# Firefly-Box.net
KiCad netlist of a schematic drawn in EAGLE
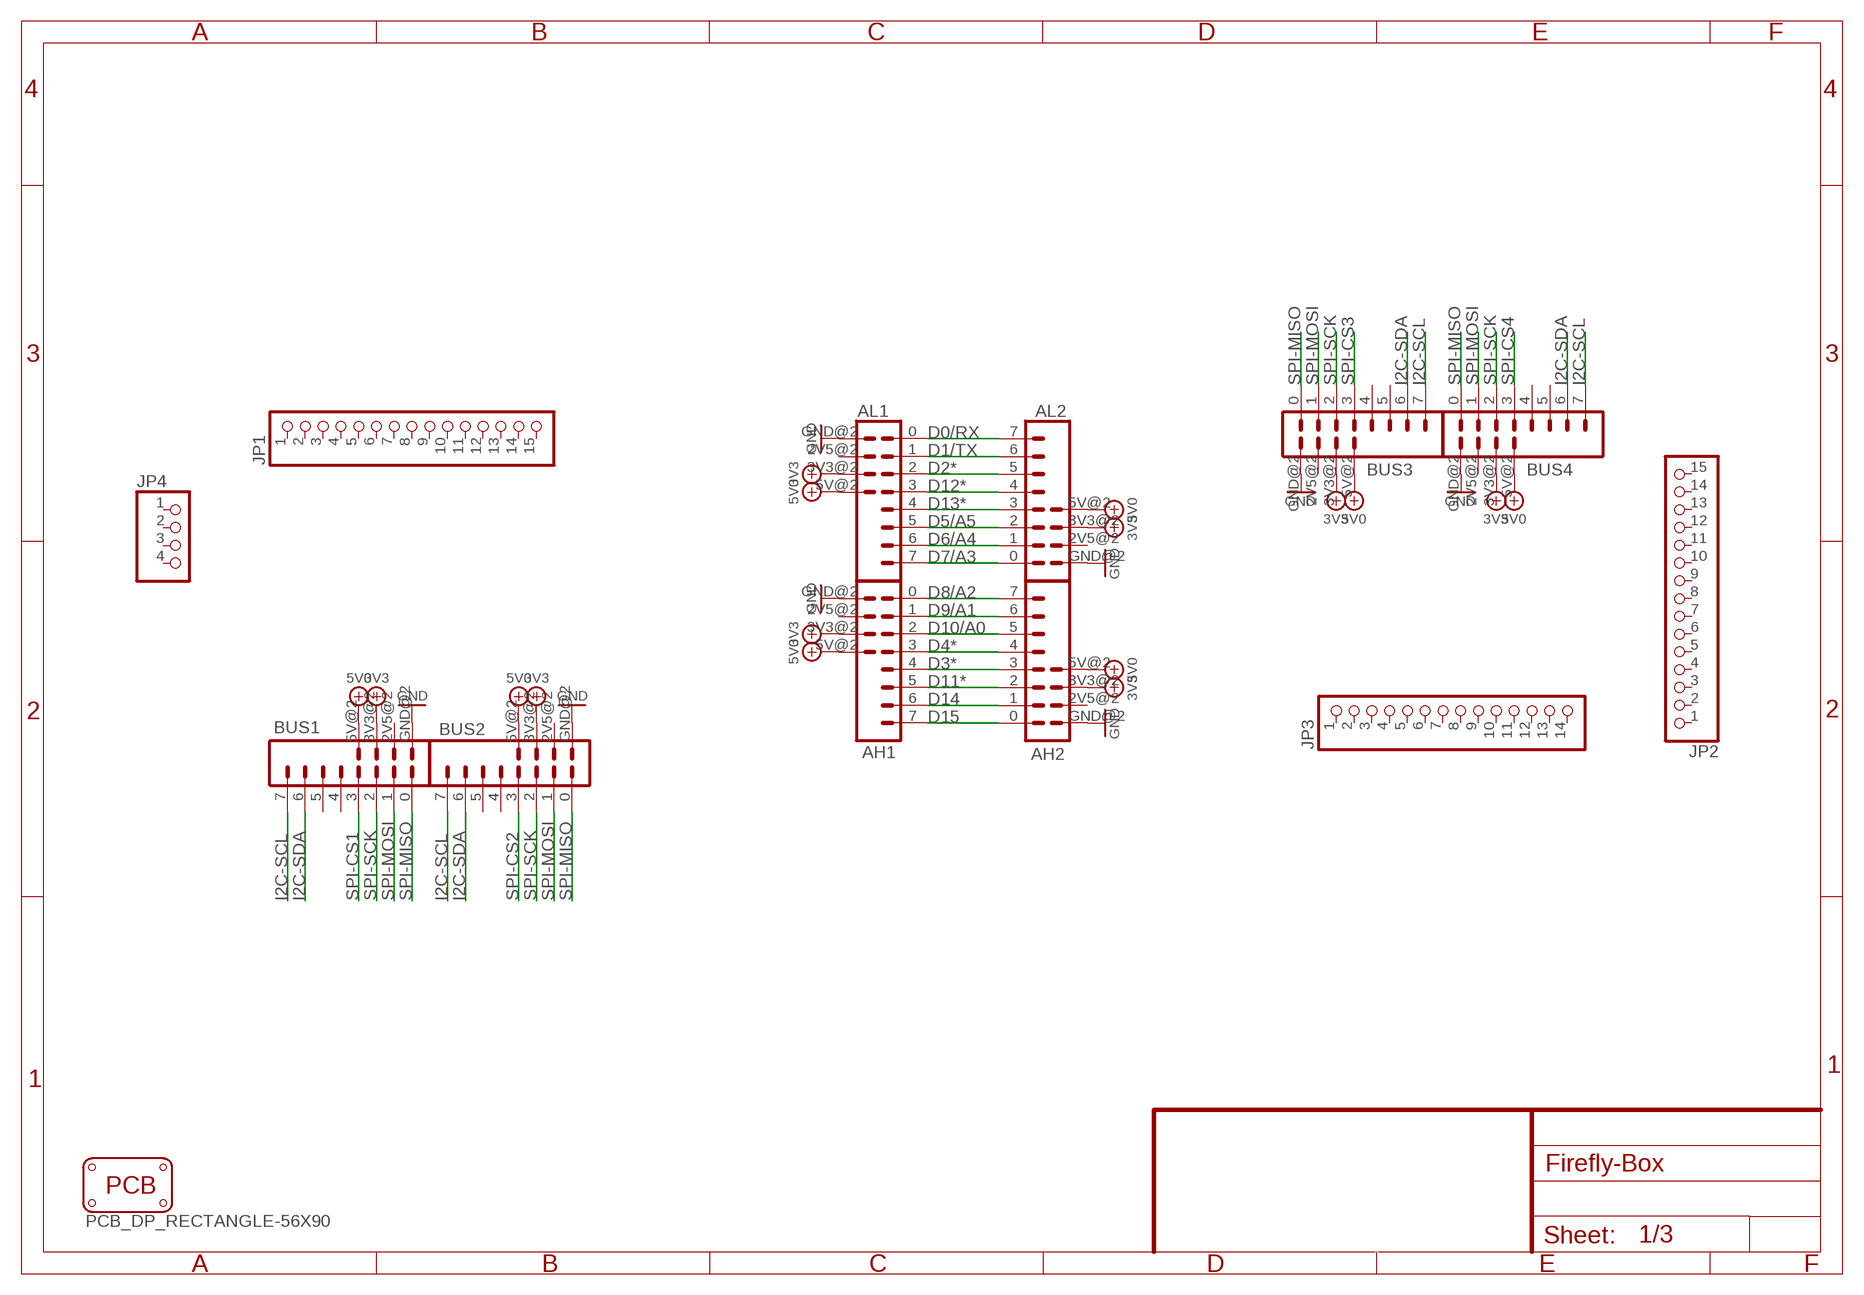
[diagram p0: schematic, sheet 1]
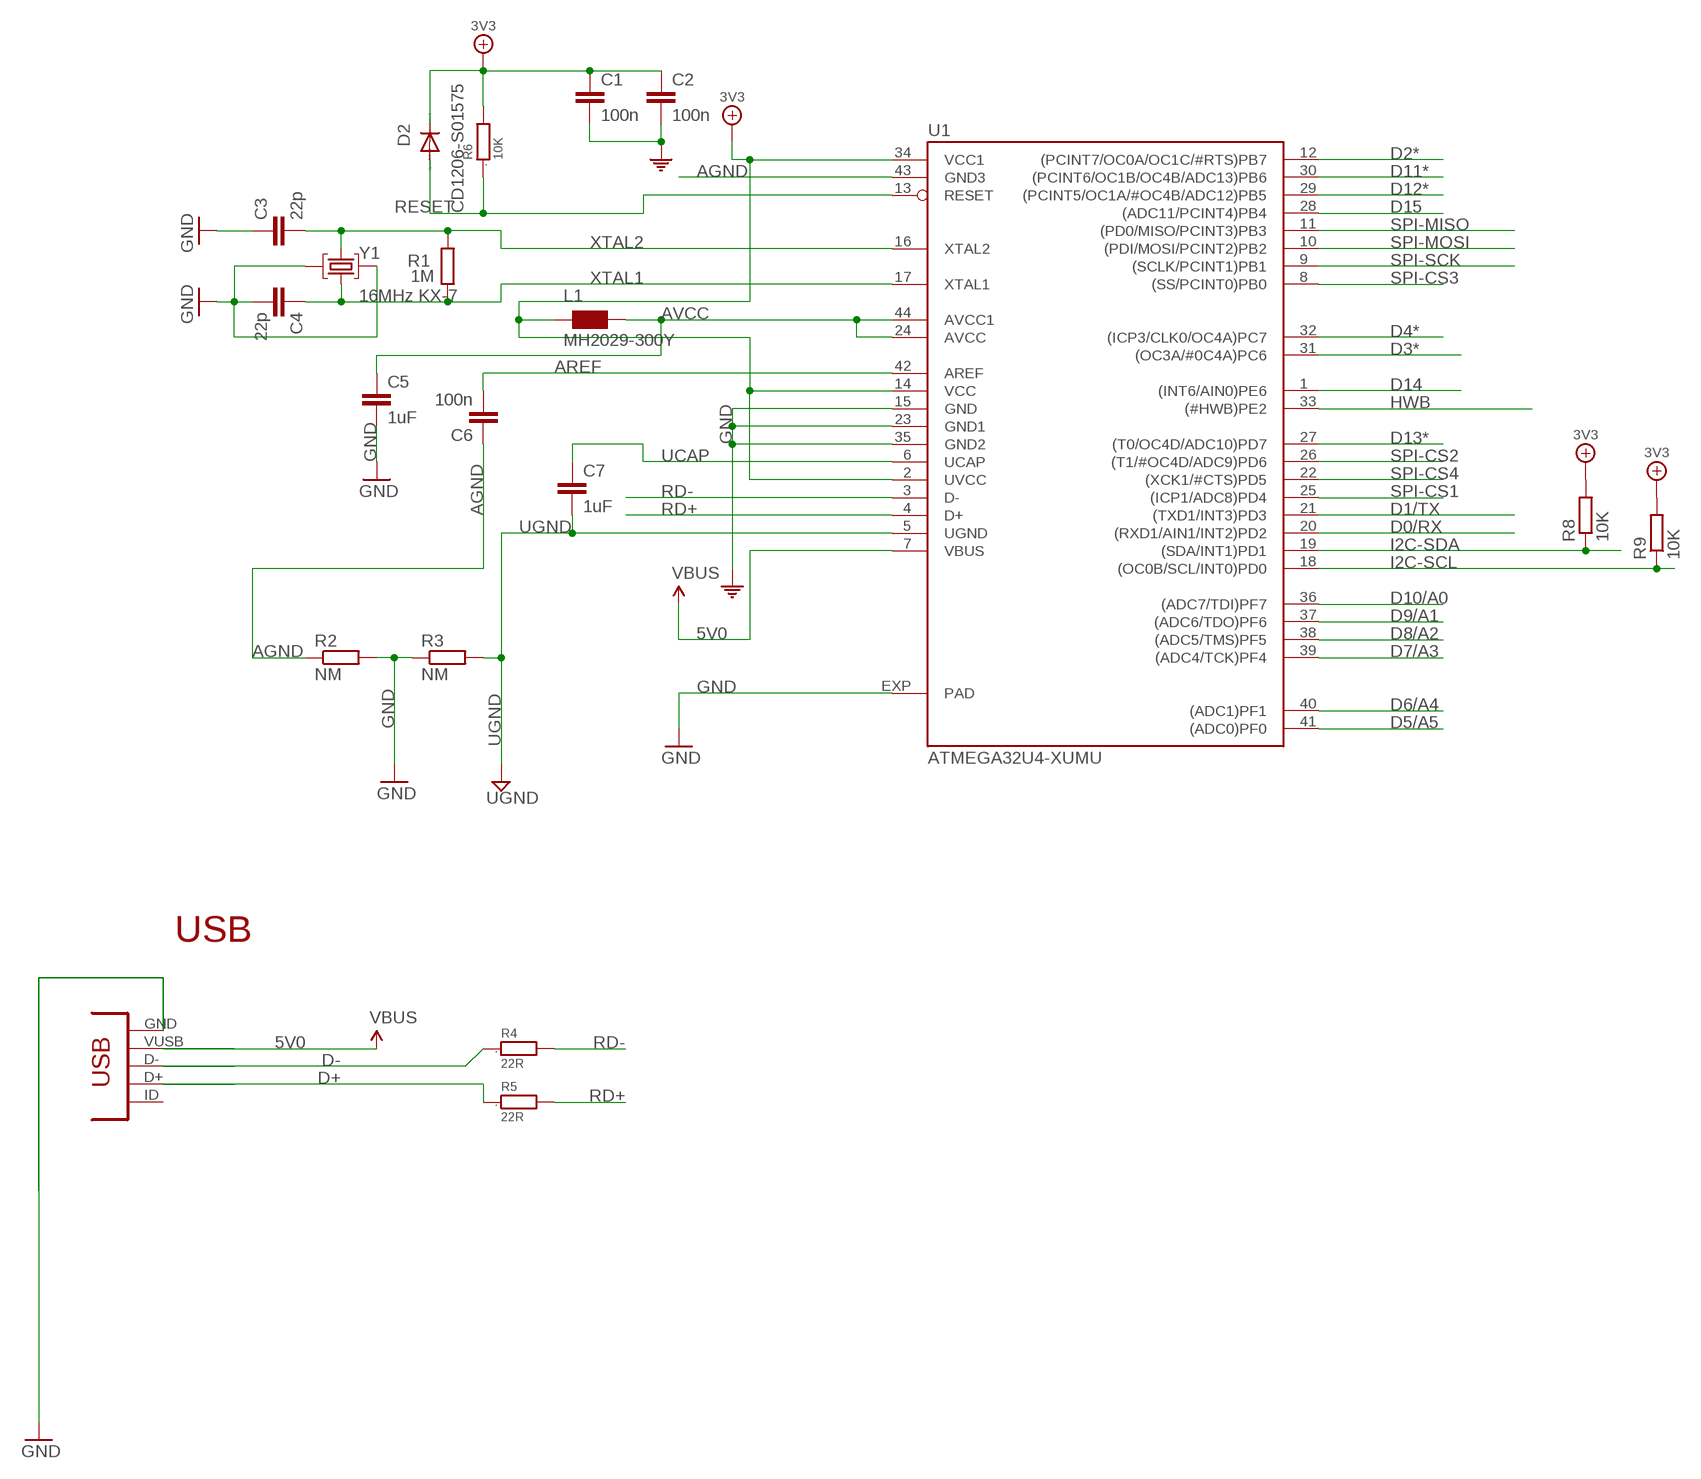
[diagram p1: schematic, sheet 2, part 1 of 2]
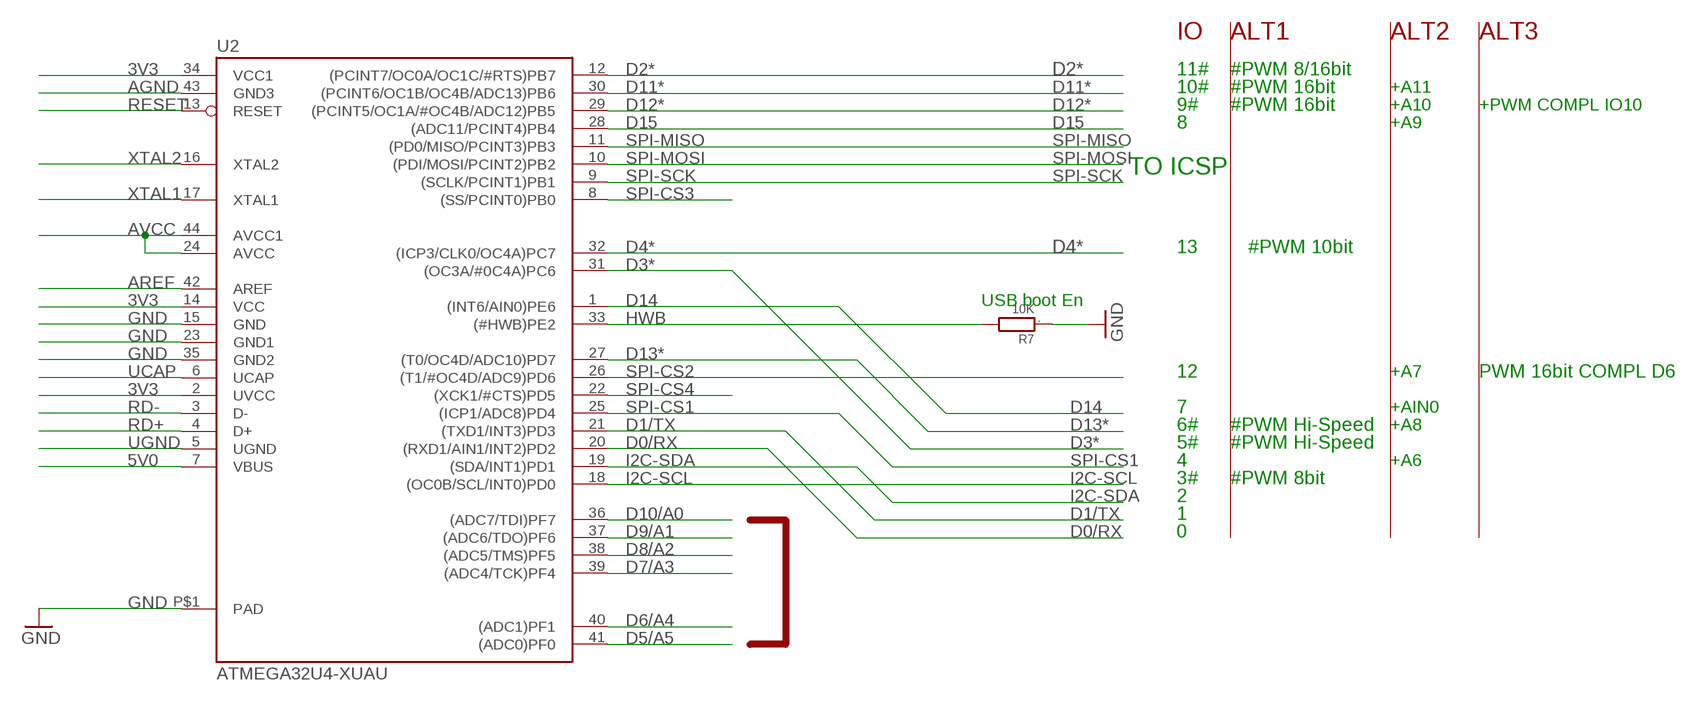
[diagram p2: schematic, sheet 2, part 2 of 2]
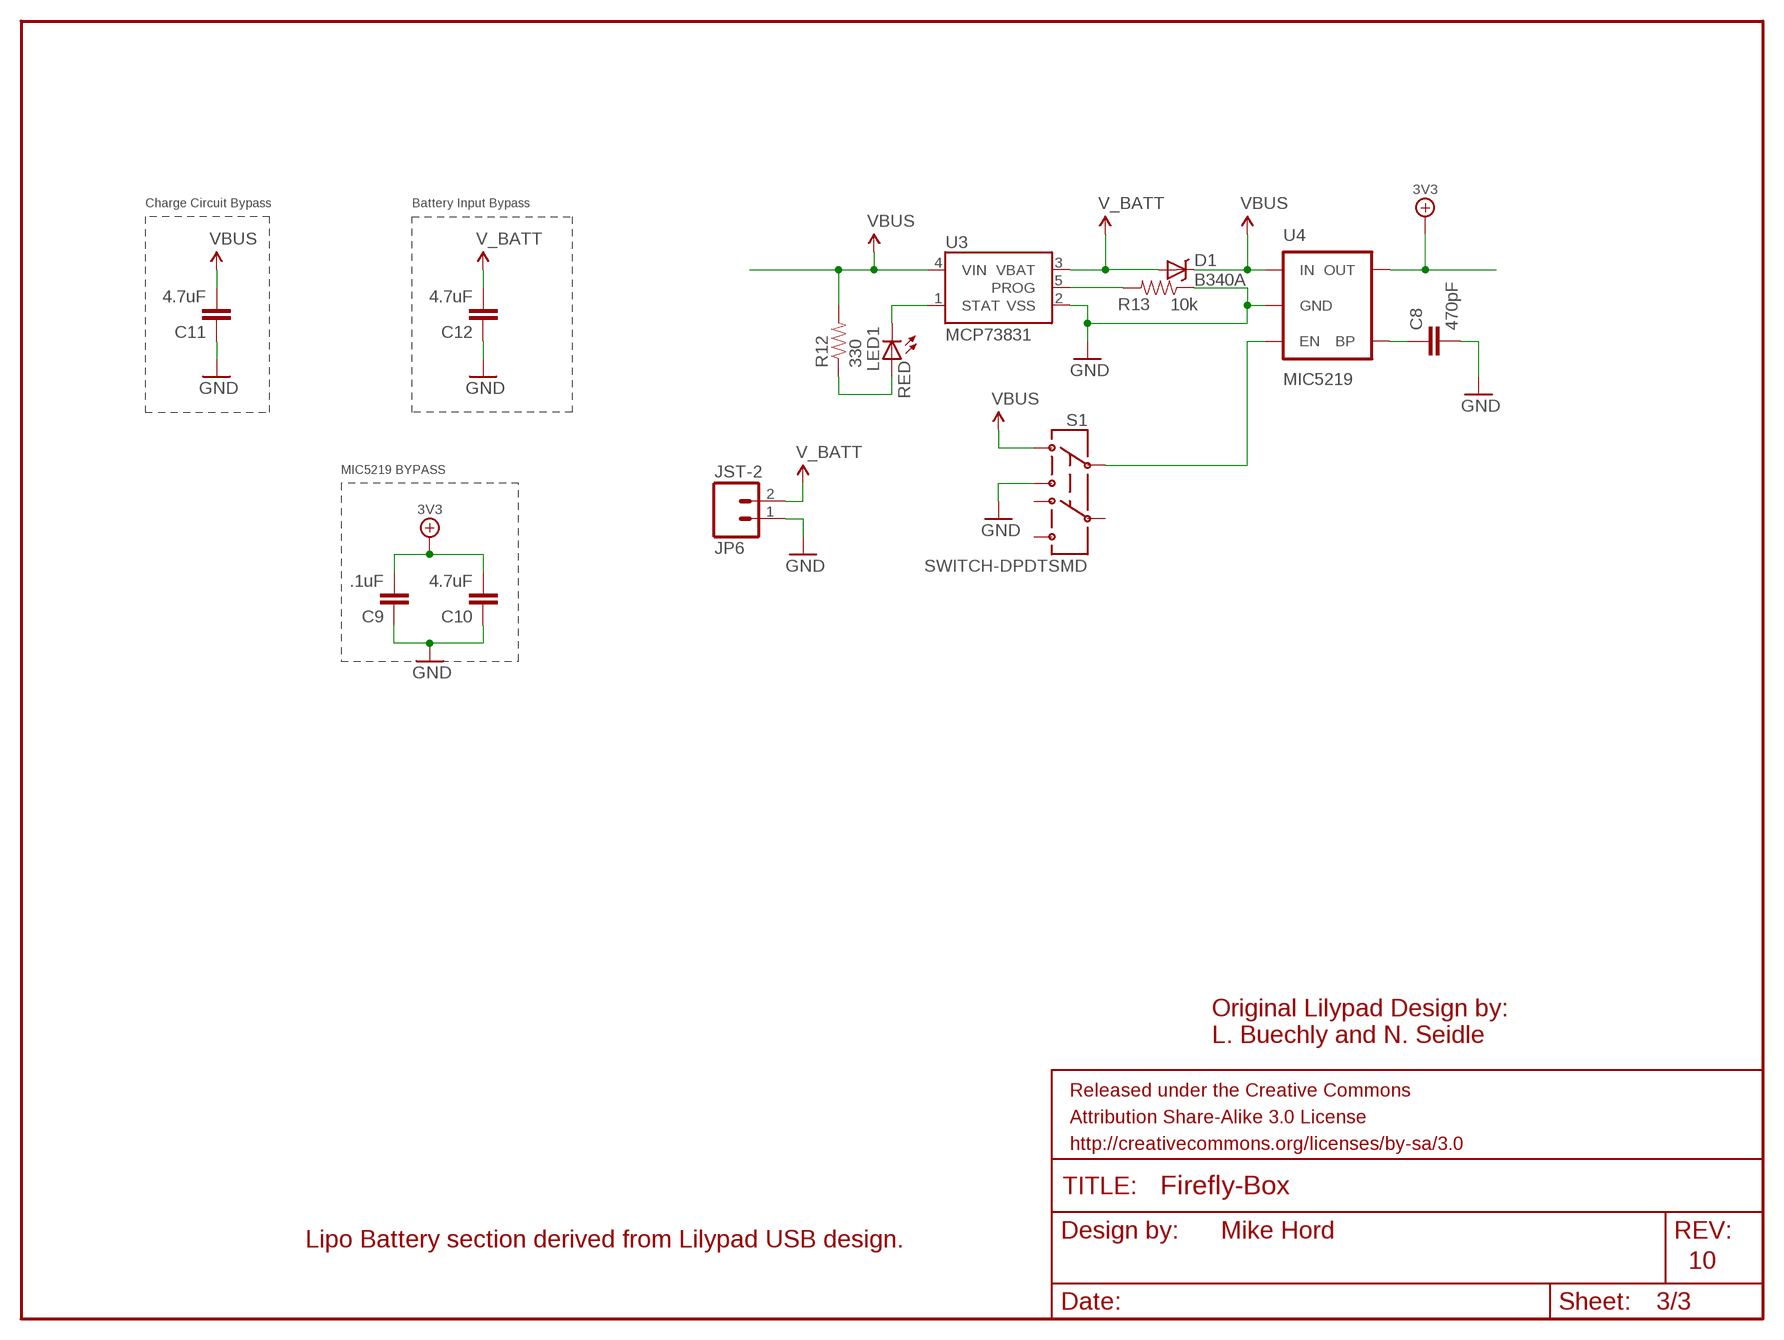
[diagram p3: schematic, sheet 3]

(export (version "E")
  (design (tool "Eeschema 10.0.6"))
  (components
    (comp (ref "AH1")
      (value "WING8WING8_NOHOLES")
      (footprint "eagle-import:WINGSIDE_8BIT_NOHOLES")
      (libsource (lib "eagle-import") (part "WING8WING8_NOHOLES"))
    )
    (comp (ref "AH2")
      (value "WING8WING8_NOHOLES")
      (footprint "eagle-import:WINGSIDE_8BIT_NOHOLES")
      (libsource (lib "eagle-import") (part "WING8WING8_NOHOLES"))
    )
    (comp (ref "AL1")
      (value "WING8WING8_NOHOLES")
      (footprint "eagle-import:WINGSIDE_8BIT_NOHOLES")
      (libsource (lib "eagle-import") (part "WING8WING8_NOHOLES"))
    )
    (comp (ref "AL2")
      (value "WING8WING8_NOHOLES")
      (footprint "eagle-import:WINGSIDE_8BIT_NOHOLES")
      (libsource (lib "eagle-import") (part "WING8WING8_NOHOLES"))
    )
    (comp (ref "BUS1")
      (value "WING8WING8_NOHOLES")
      (footprint "eagle-import:WINGSIDE_8BIT_NOHOLES")
      (libsource (lib "eagle-import") (part "WING8WING8_NOHOLES"))
    )
    (comp (ref "BUS2")
      (value "WING8WING8_NOHOLES")
      (footprint "eagle-import:WINGSIDE_8BIT_NOHOLES")
      (libsource (lib "eagle-import") (part "WING8WING8_NOHOLES"))
    )
    (comp (ref "BUS3")
      (value "WING8WING8_NOHOLES")
      (footprint "eagle-import:WINGSIDE_8BIT_NOHOLES")
      (libsource (lib "eagle-import") (part "WING8WING8_NOHOLES"))
    )
    (comp (ref "BUS4")
      (value "WING8WING8_NOHOLES")
      (footprint "eagle-import:WINGSIDE_8BIT_NOHOLES")
      (libsource (lib "eagle-import") (part "WING8WING8_NOHOLES"))
    )
    (comp (ref "JP1")
      (value "PINHD-1X15")
      (footprint "eagle-import:1X15")
      (libsource (lib "eagle-import") (part "PINHD-1X15"))
    )
    (comp (ref "JP2")
      (value "PINHD-1X15")
      (footprint "eagle-import:1X15")
      (libsource (lib "eagle-import") (part "PINHD-1X15"))
    )
    (comp (ref "JP3")
      (value "PINHD-1X14")
      (footprint "eagle-import:1X14")
      (libsource (lib "eagle-import") (part "PINHD-1X14"))
    )
    (comp (ref "JP4")
      (value "PINHD-1X4")
      (footprint "eagle-import:1X04")
      (libsource (lib "eagle-import") (part "PINHD-1X4"))
    )
    (comp (ref "PCB2")
      (value "PCB_DP_RECTANGLE-56X90")
      (footprint "eagle-import:DP9056_V1")
      (libsource (lib "eagle-import") (part "PCB_DP_RECTANGLE-56X90"))
    )
    (comp (ref "C8")
      (value "470pF")
      (footprint "eagle-import:0603-CAP")
      (libsource (lib "eagle-import") (part "CAP0603-CAP"))
    )
    (comp (ref "C9")
      (value ".1uF")
      (footprint "eagle-import:0603-CAP")
      (libsource (lib "eagle-import") (part "CAP0603-CAP"))
    )
    (comp (ref "C10")
      (value "4.7uF")
      (footprint "eagle-import:0603-CAP")
      (libsource (lib "eagle-import") (part "CAP0603-CAP"))
    )
    (comp (ref "C11")
      (value "4.7uF")
      (footprint "eagle-import:1206")
      (libsource (lib "eagle-import") (part "CAP1206"))
    )
    (comp (ref "C12")
      (value "4.7uF")
      (footprint "eagle-import:1206")
      (libsource (lib "eagle-import") (part "CAP1206"))
    )
    (comp (ref "D1")
      (value "B340A")
      (footprint "eagle-import:SMA-DIODE")
      (libsource (lib "eagle-import") (part "DIODE-SCHOTTKY_"))
    )
    (comp (ref "JP6")
      (value "JST-2")
      (footprint "eagle-import:JST-2-SMD")
      (libsource (lib "eagle-import") (part "M02-JST-2MM-SMT"))
    )
    (comp (ref "LED1")
      (value "RED")
      (footprint "eagle-import:LED-0603")
      (libsource (lib "eagle-import") (part "LED0603"))
    )
    (comp (ref "R12")
      (value "330")
      (footprint "eagle-import:0603-RES")
      (libsource (lib "eagle-import") (part "RESISTOR0603-RES"))
    )
    (comp (ref "R13")
      (value "10k")
      (footprint "eagle-import:0603-RES")
      (libsource (lib "eagle-import") (part "RESISTOR0603-RES"))
    )
    (comp (ref "S1")
      (value "SWITCH-DPDTSMD")
      (footprint "eagle-import:AYZ0202")
      (libsource (lib "eagle-import") (part "SWITCH-DPDTSMD"))
    )
    (comp (ref "U3")
      (value "MCP73831")
      (footprint "eagle-import:SOT23-5")
      (libsource (lib "eagle-import") (part "MCP73831"))
    )
    (comp (ref "U4")
      (value "MIC5219")
      (footprint "eagle-import:SOT23-5")
      (libsource (lib "eagle-import") (part "V_REG_MIC5219SMD"))
    )
    (comp (ref "C1")
      (value "100n")
      (footprint "eagle-import:C0603-ROUND")
      (libsource (lib "eagle-import") (part "C-EUC0603"))
    )
    (comp (ref "C2")
      (value "100n")
      (footprint "eagle-import:C0603-ROUND")
      (libsource (lib "eagle-import") (part "C-EUC0603"))
    )
    (comp (ref "C3")
      (value "22p")
      (footprint "eagle-import:C0603-ROUND")
      (libsource (lib "eagle-import") (part "C-EUC0603"))
    )
    (comp (ref "C4")
      (value "22p")
      (footprint "eagle-import:C0603-ROUND")
      (libsource (lib "eagle-import") (part "C-EUC0603"))
    )
    (comp (ref "C5")
      (value "1uF")
      (footprint "eagle-import:C0603-ROUND")
      (libsource (lib "eagle-import") (part "C-EUC0603"))
    )
    (comp (ref "C6")
      (value "100n")
      (footprint "eagle-import:C0603-ROUND")
      (libsource (lib "eagle-import") (part "C-EUC0603"))
    )
    (comp (ref "C7")
      (value "1uF")
      (footprint "eagle-import:C0603-ROUND")
      (libsource (lib "eagle-import") (part "C-EUC0603"))
    )
    (comp (ref "CONN2")
      (value "CONN_USB")
      (footprint "eagle-import:CONN_USB_MINI-B")
      (libsource (lib "eagle-import") (part "CONN_USB"))
    )
    (comp (ref "D2")
      (value "CD1206-S01575")
      (footprint "eagle-import:MINIMELF")
      (libsource (lib "eagle-import") (part "DIODE-MINIMELF"))
    )
    (comp (ref "L1")
      (value "MH2029-300Y")
      (footprint "eagle-import:0805")
      (libsource (lib "eagle-import") (part "WE-CBF_0805"))
    )
    (comp (ref "R1")
      (value "1M")
      (footprint "eagle-import:R0603-ROUND")
      (libsource (lib "eagle-import") (part "R-EU_R0603"))
    )
    (comp (ref "R2")
      (value "NM")
      (footprint "eagle-import:R0402")
      (libsource (lib "eagle-import") (part "R-EU_R0402"))
    )
    (comp (ref "R3")
      (value "NM")
      (footprint "eagle-import:R0402")
      (libsource (lib "eagle-import") (part "R-EU_R0402"))
    )
    (comp (ref "R4")
      (value "22R")
      (footprint "eagle-import:0805")
      (libsource (lib "eagle-import") (part "R0805"))
    )
    (comp (ref "R5")
      (value "22R")
      (footprint "eagle-import:0805")
      (libsource (lib "eagle-import") (part "R0805"))
    )
    (comp (ref "R6")
      (value "10K")
      (footprint "eagle-import:0805")
      (libsource (lib "eagle-import") (part "R0805"))
    )
    (comp (ref "R7")
      (value "10K")
      (footprint "eagle-import:0805")
      (libsource (lib "eagle-import") (part "R0805"))
    )
    (comp (ref "R8")
      (value "10K")
      (footprint "eagle-import:R0402")
      (libsource (lib "eagle-import") (part "R-EU_R0402"))
    )
    (comp (ref "R9")
      (value "10K")
      (footprint "eagle-import:R0402")
      (libsource (lib "eagle-import") (part "R-EU_R0402"))
    )
    (comp (ref "U1")
      (value "ATMEGA32U4-XUMU")
      (footprint "eagle-import:QFN44ML7X7")
      (libsource (lib "eagle-import") (part "ATMEGA32U4-XUMU"))
    )
    (comp (ref "U2")
      (value "ATMEGA32U4-XUAU")
      (footprint "eagle-import:TQFP44-PAD")
      (libsource (lib "eagle-import") (part "ATMEGA32U4-XUAU"))
    )
    (comp (ref "Y1")
      (value "16MHz KX-7")
      (footprint "eagle-import:CRYSTAL-3.2-2.5")
      (libsource (lib "eagle-import") (part "CRYSTAL-3.2-2.5"))
    )
  )
  (nets
    (net (code "1") (name "3V3") (class "Default")
      (node (ref "AH1") (pin "3V3@2") (pinfunction "3V3_3V3@2") (pintype "passive"))
      (node (ref "AH2") (pin "3V3@2") (pinfunction "3V3_3V3@2") (pintype "passive"))
      (node (ref "AL1") (pin "3V3@2") (pinfunction "3V3_3V3@2") (pintype "passive"))
      (node (ref "AL2") (pin "3V3@2") (pinfunction "3V3_3V3@2") (pintype "passive"))
      (node (ref "BUS1") (pin "3V3@2") (pinfunction "3V3_3V3@2") (pintype "passive"))
      (node (ref "BUS2") (pin "3V3@2") (pinfunction "3V3_3V3@2") (pintype "passive"))
      (node (ref "BUS3") (pin "3V3@2") (pinfunction "3V3_3V3@2") (pintype "passive"))
      (node (ref "BUS4") (pin "3V3@2") (pinfunction "3V3_3V3@2") (pintype "passive"))
      (node (ref "C1") (pin "1") (pinfunction "1_1") (pintype "passive"))
      (node (ref "C10") (pin "2") (pinfunction "2_2") (pintype "passive"))
      (node (ref "C2") (pin "1") (pinfunction "1_1") (pintype "passive"))
      (node (ref "C9") (pin "2") (pinfunction "2_2") (pintype "passive"))
      (node (ref "D2") (pin "C") (pinfunction "C_C") (pintype "passive"))
      (node (ref "L1") (pin "1") (pinfunction "1_1") (pintype "passive"))
      (node (ref "R6") (pin "2") (pinfunction "2_2") (pintype "passive"))
      (node (ref "R8") (pin "2") (pinfunction "2_2") (pintype "passive"))
      (node (ref "R9") (pin "2") (pinfunction "2_2") (pintype "passive"))
      (node (ref "U1") (pin "14") (pinfunction "VCC_14") (pintype "power_in"))
      (node (ref "U1") (pin "2") (pinfunction "UVCC_2") (pintype "power_in"))
      (node (ref "U1") (pin "34") (pinfunction "VCC1_34") (pintype "power_in"))
      (node (ref "U2") (pin "14") (pinfunction "VCC_14") (pintype "power_in"))
      (node (ref "U2") (pin "2") (pinfunction "UVCC_2") (pintype "power_in"))
      (node (ref "U2") (pin "34") (pinfunction "VCC1_34") (pintype "power_in"))
      (node (ref "U4") (pin "5") (pinfunction "OUT_5") (pintype "passive"))
    )
    (net (code "2") (name "5V0") (class "Default")
      (node (ref "AH1") (pin "5V@2") (pinfunction "5V_5V@2") (pintype "passive"))
      (node (ref "AH2") (pin "5V@2") (pinfunction "5V_5V@2") (pintype "passive"))
      (node (ref "AL1") (pin "5V@2") (pinfunction "5V_5V@2") (pintype "passive"))
      (node (ref "AL2") (pin "5V@2") (pinfunction "5V_5V@2") (pintype "passive"))
      (node (ref "BUS1") (pin "5V@2") (pinfunction "5V_5V@2") (pintype "passive"))
      (node (ref "BUS2") (pin "5V@2") (pinfunction "5V_5V@2") (pintype "passive"))
      (node (ref "BUS3") (pin "5V@2") (pinfunction "5V_5V@2") (pintype "passive"))
      (node (ref "BUS4") (pin "5V@2") (pinfunction "5V_5V@2") (pintype "passive"))
      (node (ref "C11") (pin "2") (pinfunction "2_2") (pintype "passive"))
      (node (ref "CONN2") (pin "VUSB") (pinfunction "VUSB_VUSB") (pintype "bidirectional"))
      (node (ref "D1") (pin "C") (pinfunction "C_C") (pintype "passive"))
      (node (ref "R12") (pin "2") (pinfunction "2_2") (pintype "passive"))
      (node (ref "S1") (pin "1") (pinfunction "1_1") (pintype "bidirectional"))
      (node (ref "U1") (pin "7") (pinfunction "VBUS_7") (pintype "input"))
      (node (ref "U2") (pin "7") (pinfunction "VBUS_7") (pintype "input"))
      (node (ref "U3") (pin "4") (pinfunction "VIN_4") (pintype "power_in"))
      (node (ref "U4") (pin "1") (pinfunction "IN_1") (pintype "input"))
    )
    (net (code "3") (name "AGND") (class "Default")
      (node (ref "C6") (pin "1") (pinfunction "1_1") (pintype "passive"))
      (node (ref "R2") (pin "1") (pinfunction "1_1") (pintype "passive"))
      (node (ref "U1") (pin "43") (pinfunction "GND3_43") (pintype "power_in"))
      (node (ref "U2") (pin "43") (pinfunction "GND3_43") (pintype "power_in"))
    )
    (net (code "4") (name "AREF") (class "Default")
      (node (ref "C6") (pin "2") (pinfunction "2_2") (pintype "passive"))
      (node (ref "U1") (pin "42") (pinfunction "AREF_42") (pintype "power_in"))
      (node (ref "U2") (pin "42") (pinfunction "AREF_42") (pintype "power_in"))
    )
    (net (code "5") (name "AVCC") (class "Default")
      (node (ref "C5") (pin "1") (pinfunction "1_1") (pintype "passive"))
      (node (ref "L1") (pin "2") (pinfunction "2_2") (pintype "passive"))
      (node (ref "U1") (pin "24") (pinfunction "AVCC_24") (pintype "power_in"))
      (node (ref "U1") (pin "44") (pinfunction "AVCC1_44") (pintype "power_in"))
      (node (ref "U2") (pin "24") (pinfunction "AVCC_24") (pintype "power_in"))
      (node (ref "U2") (pin "44") (pinfunction "AVCC1_44") (pintype "power_in"))
    )
    (net (code "6") (name "D+") (class "Default")
      (node (ref "CONN2") (pin "D+") (pinfunction "D+_D+") (pintype "bidirectional"))
      (node (ref "R5") (pin "1") (pinfunction "1_1") (pintype "passive"))
    )
    (net (code "7") (name "D-") (class "Default")
      (node (ref "CONN2") (pin "D-") (pinfunction "D-_D-") (pintype "bidirectional"))
      (node (ref "R4") (pin "1") (pinfunction "1_1") (pintype "passive"))
    )
    (net (code "8") (name "D0{slash}RX") (class "Default")
      (node (ref "AL1") (pin "0") (pinfunction "1_0") (pintype "passive"))
      (node (ref "AL2") (pin "7") (pinfunction "8_7") (pintype "passive"))
      (node (ref "U1") (pin "20") (pinfunction "(RXD1/AIN1/INT2)PD2_20") (pintype "bidirectional"))
      (node (ref "U2") (pin "20") (pinfunction "(RXD1/AIN1/INT2)PD2_20") (pintype "bidirectional"))
    )
    (net (code "9") (name "D1{slash}TX") (class "Default")
      (node (ref "AL1") (pin "1") (pinfunction "2_1") (pintype "passive"))
      (node (ref "AL2") (pin "6") (pinfunction "7_6") (pintype "passive"))
      (node (ref "U1") (pin "21") (pinfunction "(TXD1/INT3)PD3_21") (pintype "bidirectional"))
      (node (ref "U2") (pin "21") (pinfunction "(TXD1/INT3)PD3_21") (pintype "bidirectional"))
    )
    (net (code "10") (name "D2*") (class "Default")
      (node (ref "AL1") (pin "2") (pinfunction "3_2") (pintype "passive"))
      (node (ref "AL2") (pin "5") (pinfunction "6_5") (pintype "passive"))
      (node (ref "U1") (pin "12") (pinfunction "(PCINT7/OC0A/OC1C/#RTS)PB7_12") (pintype "bidirectional"))
      (node (ref "U2") (pin "12") (pinfunction "(PCINT7/OC0A/OC1C/#RTS)PB7_12") (pintype "bidirectional"))
    )
    (net (code "11") (name "D3*") (class "Default")
      (node (ref "AH1") (pin "4") (pinfunction "5_4") (pintype "passive"))
      (node (ref "AH2") (pin "3") (pinfunction "4_3") (pintype "passive"))
      (node (ref "U1") (pin "31") (pinfunction "(OC3A/#0C4A)PC6_31") (pintype "bidirectional"))
      (node (ref "U2") (pin "31") (pinfunction "(OC3A/#0C4A)PC6_31") (pintype "bidirectional"))
    )
    (net (code "12") (name "D4*") (class "Default")
      (node (ref "AH1") (pin "3") (pinfunction "4_3") (pintype "passive"))
      (node (ref "AH2") (pin "4") (pinfunction "5_4") (pintype "passive"))
      (node (ref "U1") (pin "32") (pinfunction "(ICP3/CLK0/OC4A)PC7_32") (pintype "bidirectional"))
      (node (ref "U2") (pin "32") (pinfunction "(ICP3/CLK0/OC4A)PC7_32") (pintype "bidirectional"))
    )
    (net (code "13") (name "D5{slash}A5") (class "Default")
      (node (ref "AL1") (pin "5") (pinfunction "6_5") (pintype "passive"))
      (node (ref "AL2") (pin "2") (pinfunction "3_2") (pintype "passive"))
      (node (ref "U1") (pin "41") (pinfunction "(ADC0)PF0_41") (pintype "bidirectional"))
      (node (ref "U2") (pin "41") (pinfunction "(ADC0)PF0_41") (pintype "bidirectional"))
    )
    (net (code "14") (name "D6{slash}A4") (class "Default")
      (node (ref "AL1") (pin "6") (pinfunction "7_6") (pintype "passive"))
      (node (ref "AL2") (pin "1") (pinfunction "2_1") (pintype "passive"))
      (node (ref "U1") (pin "40") (pinfunction "(ADC1)PF1_40") (pintype "bidirectional"))
      (node (ref "U2") (pin "40") (pinfunction "(ADC1)PF1_40") (pintype "bidirectional"))
    )
    (net (code "15") (name "D7{slash}A3") (class "Default")
      (node (ref "AL1") (pin "7") (pinfunction "8_7") (pintype "passive"))
      (node (ref "AL2") (pin "0") (pinfunction "1_0") (pintype "passive"))
      (node (ref "U1") (pin "39") (pinfunction "(ADC4/TCK)PF4_39") (pintype "bidirectional"))
      (node (ref "U2") (pin "39") (pinfunction "(ADC4/TCK)PF4_39") (pintype "bidirectional"))
    )
    (net (code "16") (name "D8{slash}A2") (class "Default")
      (node (ref "AH1") (pin "0") (pinfunction "1_0") (pintype "passive"))
      (node (ref "AH2") (pin "7") (pinfunction "8_7") (pintype "passive"))
      (node (ref "U1") (pin "38") (pinfunction "(ADC5/TMS)PF5_38") (pintype "bidirectional"))
      (node (ref "U2") (pin "38") (pinfunction "(ADC5/TMS)PF5_38") (pintype "bidirectional"))
    )
    (net (code "17") (name "D9{slash}A1") (class "Default")
      (node (ref "AH1") (pin "1") (pinfunction "2_1") (pintype "passive"))
      (node (ref "AH2") (pin "6") (pinfunction "7_6") (pintype "passive"))
      (node (ref "U1") (pin "37") (pinfunction "(ADC6/TDO)PF6_37") (pintype "bidirectional"))
      (node (ref "U2") (pin "37") (pinfunction "(ADC6/TDO)PF6_37") (pintype "bidirectional"))
    )
    (net (code "18") (name "D10{slash}A0") (class "Default")
      (node (ref "AH1") (pin "2") (pinfunction "3_2") (pintype "passive"))
      (node (ref "AH2") (pin "5") (pinfunction "6_5") (pintype "passive"))
      (node (ref "U1") (pin "36") (pinfunction "(ADC7/TDI)PF7_36") (pintype "bidirectional"))
      (node (ref "U2") (pin "36") (pinfunction "(ADC7/TDI)PF7_36") (pintype "bidirectional"))
    )
    (net (code "19") (name "D11*") (class "Default")
      (node (ref "AH1") (pin "5") (pinfunction "6_5") (pintype "passive"))
      (node (ref "AH2") (pin "2") (pinfunction "3_2") (pintype "passive"))
      (node (ref "U1") (pin "30") (pinfunction "(PCINT6/OC1B/OC4B/ADC13)PB6_30") (pintype "bidirectional"))
      (node (ref "U2") (pin "30") (pinfunction "(PCINT6/OC1B/OC4B/ADC13)PB6_30") (pintype "bidirectional"))
    )
    (net (code "20") (name "D12*") (class "Default")
      (node (ref "AL1") (pin "3") (pinfunction "4_3") (pintype "passive"))
      (node (ref "AL2") (pin "4") (pinfunction "5_4") (pintype "passive"))
      (node (ref "U1") (pin "29") (pinfunction "(PCINT5/OC1A/#OC4B/ADC12)PB5_29") (pintype "bidirectional"))
      (node (ref "U2") (pin "29") (pinfunction "(PCINT5/OC1A/#OC4B/ADC12)PB5_29") (pintype "bidirectional"))
    )
    (net (code "21") (name "D13*") (class "Default")
      (node (ref "AL1") (pin "4") (pinfunction "5_4") (pintype "passive"))
      (node (ref "AL2") (pin "3") (pinfunction "4_3") (pintype "passive"))
      (node (ref "U1") (pin "27") (pinfunction "(T0/OC4D/ADC10)PD7_27") (pintype "bidirectional"))
      (node (ref "U2") (pin "27") (pinfunction "(T0/OC4D/ADC10)PD7_27") (pintype "bidirectional"))
    )
    (net (code "22") (name "D14") (class "Default")
      (node (ref "AH1") (pin "6") (pinfunction "7_6") (pintype "passive"))
      (node (ref "AH2") (pin "1") (pinfunction "2_1") (pintype "passive"))
      (node (ref "U1") (pin "1") (pinfunction "(INT6/AIN0)PE6_1") (pintype "bidirectional"))
      (node (ref "U2") (pin "1") (pinfunction "(INT6/AIN0)PE6_1") (pintype "bidirectional"))
    )
    (net (code "23") (name "D15") (class "Default")
      (node (ref "AH1") (pin "7") (pinfunction "8_7") (pintype "passive"))
      (node (ref "AH2") (pin "0") (pinfunction "1_0") (pintype "passive"))
      (node (ref "U1") (pin "28") (pinfunction "(ADC11/PCINT4)PB4_28") (pintype "bidirectional"))
      (node (ref "U2") (pin "28") (pinfunction "(ADC11/PCINT4)PB4_28") (pintype "bidirectional"))
    )
    (net (code "24") (name "GND") (class "Default")
      (node (ref "AH1") (pin "GND@2") (pinfunction "GND_GND@2") (pintype "passive"))
      (node (ref "AH2") (pin "GND@2") (pinfunction "GND_GND@2") (pintype "passive"))
      (node (ref "AL1") (pin "GND@2") (pinfunction "GND_GND@2") (pintype "passive"))
      (node (ref "AL2") (pin "GND@2") (pinfunction "GND_GND@2") (pintype "passive"))
      (node (ref "BUS1") (pin "GND@2") (pinfunction "GND_GND@2") (pintype "passive"))
      (node (ref "BUS2") (pin "GND@2") (pinfunction "GND_GND@2") (pintype "passive"))
      (node (ref "BUS3") (pin "GND@2") (pinfunction "GND_GND@2") (pintype "passive"))
      (node (ref "BUS4") (pin "GND@2") (pinfunction "GND_GND@2") (pintype "passive"))
      (node (ref "C1") (pin "2") (pinfunction "2_2") (pintype "passive"))
      (node (ref "C10") (pin "1") (pinfunction "1_1") (pintype "passive"))
      (node (ref "C11") (pin "1") (pinfunction "1_1") (pintype "passive"))
      (node (ref "C12") (pin "1") (pinfunction "1_1") (pintype "passive"))
      (node (ref "C2") (pin "2") (pinfunction "2_2") (pintype "passive"))
      (node (ref "C3") (pin "1") (pinfunction "1_1") (pintype "passive"))
      (node (ref "C4") (pin "2") (pinfunction "2_2") (pintype "passive"))
      (node (ref "C5") (pin "2") (pinfunction "2_2") (pintype "passive"))
      (node (ref "C8") (pin "2") (pinfunction "2_2") (pintype "passive"))
      (node (ref "C9") (pin "1") (pinfunction "1_1") (pintype "passive"))
      (node (ref "CONN2") (pin "GND") (pinfunction "GND_GND") (pintype "bidirectional"))
      (node (ref "JP6") (pin "1") (pinfunction "2_1") (pintype "passive"))
      (node (ref "R13") (pin "1") (pinfunction "1_1") (pintype "passive"))
      (node (ref "R2") (pin "2") (pinfunction "2_2") (pintype "passive"))
      (node (ref "R3") (pin "1") (pinfunction "1_1") (pintype "passive"))
      (node (ref "R7") (pin "1") (pinfunction "1_1") (pintype "passive"))
      (node (ref "S1") (pin "3") (pinfunction "3_3") (pintype "bidirectional"))
      (node (ref "U1") (pin "15") (pinfunction "GND_15") (pintype "power_in"))
      (node (ref "U1") (pin "23") (pinfunction "GND1_23") (pintype "power_in"))
      (node (ref "U1") (pin "35") (pinfunction "GND2_35") (pintype "power_in"))
      (node (ref "U1") (pin "EXP") (pinfunction "PAD_EXP") (pintype "power_in"))
      (node (ref "U2") (pin "15") (pinfunction "GND_15") (pintype "power_in"))
      (node (ref "U2") (pin "23") (pinfunction "GND1_23") (pintype "power_in"))
      (node (ref "U2") (pin "35") (pinfunction "GND2_35") (pintype "power_in"))
      (node (ref "U2") (pin "P$1") (pinfunction "PAD_P$1") (pintype "power_in"))
      (node (ref "U3") (pin "2") (pinfunction "VSS_2") (pintype "power_in"))
      (node (ref "U4") (pin "2") (pinfunction "GND_2") (pintype "input"))
      (node (ref "Y1") (pin "2") (pinfunction "GND_2") (pintype "passive"))
      (node (ref "Y1") (pin "4") (pinfunction "GND_4") (pintype "passive"))
    )
    (net (code "25") (name "HWB") (class "Default")
      (node (ref "R7") (pin "2") (pinfunction "2_2") (pintype "passive"))
      (node (ref "U1") (pin "33") (pinfunction "(#HWB)PE2_33") (pintype "bidirectional"))
      (node (ref "U2") (pin "33") (pinfunction "(#HWB)PE2_33") (pintype "bidirectional"))
    )
    (net (code "26") (name "I2C-SCL") (class "Default")
      (node (ref "BUS1") (pin "7") (pinfunction "8_7") (pintype "passive"))
      (node (ref "BUS2") (pin "7") (pinfunction "8_7") (pintype "passive"))
      (node (ref "BUS3") (pin "7") (pinfunction "8_7") (pintype "passive"))
      (node (ref "BUS4") (pin "7") (pinfunction "8_7") (pintype "passive"))
      (node (ref "R9") (pin "1") (pinfunction "1_1") (pintype "passive"))
      (node (ref "U1") (pin "18") (pinfunction "(OC0B/SCL/INT0)PD0_18") (pintype "bidirectional"))
      (node (ref "U2") (pin "18") (pinfunction "(OC0B/SCL/INT0)PD0_18") (pintype "bidirectional"))
    )
    (net (code "27") (name "I2C-SDA") (class "Default")
      (node (ref "BUS1") (pin "6") (pinfunction "7_6") (pintype "passive"))
      (node (ref "BUS2") (pin "6") (pinfunction "7_6") (pintype "passive"))
      (node (ref "BUS3") (pin "6") (pinfunction "7_6") (pintype "passive"))
      (node (ref "BUS4") (pin "6") (pinfunction "7_6") (pintype "passive"))
      (node (ref "R8") (pin "1") (pinfunction "1_1") (pintype "passive"))
      (node (ref "U1") (pin "19") (pinfunction "(SDA/INT1)PD1_19") (pintype "bidirectional"))
      (node (ref "U2") (pin "19") (pinfunction "(SDA/INT1)PD1_19") (pintype "bidirectional"))
    )
    (net (code "28") (name "Net-(LED1-PadA)") (class "Default")
      (node (ref "LED1") (pin "A") (pinfunction "A_A") (pintype "passive"))
      (node (ref "R12") (pin "1") (pinfunction "1_1") (pintype "passive"))
    )
    (net (code "29") (name "Net-(U3-PROG)") (class "Default")
      (node (ref "R13") (pin "2") (pinfunction "2_2") (pintype "passive"))
      (node (ref "U3") (pin "5") (pinfunction "PROG_5") (pintype "input"))
    )
    (net (code "30") (name "Net-(U3-STAT)") (class "Default")
      (node (ref "LED1") (pin "C") (pinfunction "C_C") (pintype "passive"))
      (node (ref "U3") (pin "1") (pinfunction "STAT_1") (pintype "output"))
    )
    (net (code "31") (name "Net-(U4-BP)") (class "Default")
      (node (ref "C8") (pin "1") (pinfunction "1_1") (pintype "passive"))
      (node (ref "U4") (pin "4") (pinfunction "BP_4") (pintype "input"))
    )
    (net (code "32") (name "Net-(U4-EN)") (class "Default")
      (node (ref "S1") (pin "2") (pinfunction "2_2") (pintype "bidirectional"))
      (node (ref "U4") (pin "3") (pinfunction "EN_3") (pintype "input"))
    )
    (net (code "33") (name "RD+") (class "Default")
      (node (ref "R5") (pin "2") (pinfunction "2_2") (pintype "passive"))
      (node (ref "U1") (pin "4") (pinfunction "D+_4") (pintype "bidirectional"))
      (node (ref "U2") (pin "4") (pinfunction "D+_4") (pintype "bidirectional"))
    )
    (net (code "34") (name "RD-") (class "Default")
      (node (ref "R4") (pin "2") (pinfunction "2_2") (pintype "passive"))
      (node (ref "U1") (pin "3") (pinfunction "D-_3") (pintype "bidirectional"))
      (node (ref "U2") (pin "3") (pinfunction "D-_3") (pintype "bidirectional"))
    )
    (net (code "35") (name "RESET") (class "Default")
      (node (ref "D2") (pin "A") (pinfunction "A_A") (pintype "passive"))
      (node (ref "R6") (pin "1") (pinfunction "1_1") (pintype "passive"))
      (node (ref "U1") (pin "13") (pinfunction "RESET_13") (pintype "input"))
      (node (ref "U2") (pin "13") (pinfunction "RESET_13") (pintype "input"))
    )
    (net (code "36") (name "SPI-CS1") (class "Default")
      (node (ref "BUS1") (pin "3") (pinfunction "4_3") (pintype "passive"))
      (node (ref "U1") (pin "25") (pinfunction "(ICP1/ADC8)PD4_25") (pintype "bidirectional"))
      (node (ref "U2") (pin "25") (pinfunction "(ICP1/ADC8)PD4_25") (pintype "bidirectional"))
    )
    (net (code "37") (name "SPI-CS2") (class "Default")
      (node (ref "BUS2") (pin "3") (pinfunction "4_3") (pintype "passive"))
      (node (ref "U1") (pin "26") (pinfunction "(T1/#OC4D/ADC9)PD6_26") (pintype "bidirectional"))
      (node (ref "U2") (pin "26") (pinfunction "(T1/#OC4D/ADC9)PD6_26") (pintype "bidirectional"))
    )
    (net (code "38") (name "SPI-CS3") (class "Default")
      (node (ref "BUS3") (pin "3") (pinfunction "4_3") (pintype "passive"))
      (node (ref "U1") (pin "8") (pinfunction "(SS/PCINT0)PB0_8") (pintype "bidirectional"))
      (node (ref "U2") (pin "8") (pinfunction "(SS/PCINT0)PB0_8") (pintype "bidirectional"))
    )
    (net (code "39") (name "SPI-CS4") (class "Default")
      (node (ref "BUS4") (pin "3") (pinfunction "4_3") (pintype "passive"))
      (node (ref "U1") (pin "22") (pinfunction "(XCK1/#CTS)PD5_22") (pintype "bidirectional"))
      (node (ref "U2") (pin "22") (pinfunction "(XCK1/#CTS)PD5_22") (pintype "bidirectional"))
    )
    (net (code "40") (name "SPI-MISO") (class "Default")
      (node (ref "BUS1") (pin "0") (pinfunction "1_0") (pintype "passive"))
      (node (ref "BUS2") (pin "0") (pinfunction "1_0") (pintype "passive"))
      (node (ref "BUS3") (pin "0") (pinfunction "1_0") (pintype "passive"))
      (node (ref "BUS4") (pin "0") (pinfunction "1_0") (pintype "passive"))
      (node (ref "U1") (pin "11") (pinfunction "(PD0/MISO/PCINT3)PB3_11") (pintype "bidirectional"))
      (node (ref "U2") (pin "11") (pinfunction "(PD0/MISO/PCINT3)PB3_11") (pintype "bidirectional"))
    )
    (net (code "41") (name "SPI-MOSI") (class "Default")
      (node (ref "BUS1") (pin "1") (pinfunction "2_1") (pintype "passive"))
      (node (ref "BUS2") (pin "1") (pinfunction "2_1") (pintype "passive"))
      (node (ref "BUS3") (pin "1") (pinfunction "2_1") (pintype "passive"))
      (node (ref "BUS4") (pin "1") (pinfunction "2_1") (pintype "passive"))
      (node (ref "U1") (pin "10") (pinfunction "(PDI/MOSI/PCINT2)PB2_10") (pintype "bidirectional"))
      (node (ref "U2") (pin "10") (pinfunction "(PDI/MOSI/PCINT2)PB2_10") (pintype "bidirectional"))
    )
    (net (code "42") (name "SPI-SCK") (class "Default")
      (node (ref "BUS1") (pin "2") (pinfunction "3_2") (pintype "passive"))
      (node (ref "BUS2") (pin "2") (pinfunction "3_2") (pintype "passive"))
      (node (ref "BUS3") (pin "2") (pinfunction "3_2") (pintype "passive"))
      (node (ref "BUS4") (pin "2") (pinfunction "3_2") (pintype "passive"))
      (node (ref "U1") (pin "9") (pinfunction "(SCLK/PCINT1)PB1_9") (pintype "bidirectional"))
      (node (ref "U2") (pin "9") (pinfunction "(SCLK/PCINT1)PB1_9") (pintype "bidirectional"))
    )
    (net (code "43") (name "UCAP") (class "Default")
      (node (ref "C7") (pin "1") (pinfunction "1_1") (pintype "passive"))
      (node (ref "U1") (pin "6") (pinfunction "UCAP_6") (pintype "passive"))
      (node (ref "U2") (pin "6") (pinfunction "UCAP_6") (pintype "passive"))
    )
    (net (code "44") (name "UGND") (class "Default")
      (node (ref "C7") (pin "2") (pinfunction "2_2") (pintype "passive"))
      (node (ref "R3") (pin "2") (pinfunction "2_2") (pintype "passive"))
      (node (ref "U1") (pin "5") (pinfunction "UGND_5") (pintype "power_in"))
      (node (ref "U2") (pin "5") (pinfunction "UGND_5") (pintype "power_in"))
    )
    (net (code "45") (name "V_BATT") (class "Default")
      (node (ref "C12") (pin "2") (pinfunction "2_2") (pintype "passive"))
      (node (ref "D1") (pin "A") (pinfunction "A_A") (pintype "passive"))
      (node (ref "JP6") (pin "2") (pinfunction "1_2") (pintype "passive"))
      (node (ref "U3") (pin "3") (pinfunction "VBAT_3") (pintype "power_in"))
    )
    (net (code "46") (name "XTAL1") (class "Default")
      (node (ref "C4") (pin "1") (pinfunction "1_1") (pintype "passive"))
      (node (ref "R1") (pin "1") (pinfunction "1_1") (pintype "passive"))
      (node (ref "U1") (pin "17") (pinfunction "XTAL1_17") (pintype "bidirectional"))
      (node (ref "U2") (pin "17") (pinfunction "XTAL1_17") (pintype "bidirectional"))
      (node (ref "Y1") (pin "1") (pinfunction "C1_1") (pintype "passive"))
    )
    (net (code "47") (name "XTAL2") (class "Default")
      (node (ref "C3") (pin "2") (pinfunction "2_2") (pintype "passive"))
      (node (ref "R1") (pin "2") (pinfunction "2_2") (pintype "passive"))
      (node (ref "U1") (pin "16") (pinfunction "XTAL2_16") (pintype "bidirectional"))
      (node (ref "U2") (pin "16") (pinfunction "XTAL2_16") (pintype "bidirectional"))
      (node (ref "Y1") (pin "3") (pinfunction "C2_3") (pintype "passive"))
    )
    (net (code "48") (name "unconnected-(AH1-2V5-Pad2V5@2)") (class "Default")
      (node (ref "AH1") (pin "2V5@2") (pinfunction "2V5_2V5@2") (pintype "passive"))
    )
    (net (code "49") (name "unconnected-(AH2-2V5-Pad2V5@2)") (class "Default")
      (node (ref "AH2") (pin "2V5@2") (pinfunction "2V5_2V5@2") (pintype "passive"))
    )
    (net (code "50") (name "unconnected-(AL1-2V5-Pad2V5@2)") (class "Default")
      (node (ref "AL1") (pin "2V5@2") (pinfunction "2V5_2V5@2") (pintype "passive"))
    )
    (net (code "51") (name "unconnected-(AL2-2V5-Pad2V5@2)") (class "Default")
      (node (ref "AL2") (pin "2V5@2") (pinfunction "2V5_2V5@2") (pintype "passive"))
    )
    (net (code "52") (name "unconnected-(BUS1-2V5-Pad2V5@2)") (class "Default")
      (node (ref "BUS1") (pin "2V5@2") (pinfunction "2V5_2V5@2") (pintype "passive"))
    )
    (net (code "53") (name "unconnected-(BUS1-5-Pad4)") (class "Default")
      (node (ref "BUS1") (pin "4") (pinfunction "5_4") (pintype "passive"))
    )
    (net (code "54") (name "unconnected-(BUS1-6-Pad5)") (class "Default")
      (node (ref "BUS1") (pin "5") (pinfunction "6_5") (pintype "passive"))
    )
    (net (code "55") (name "unconnected-(BUS2-2V5-Pad2V5@2)") (class "Default")
      (node (ref "BUS2") (pin "2V5@2") (pinfunction "2V5_2V5@2") (pintype "passive"))
    )
    (net (code "56") (name "unconnected-(BUS2-5-Pad4)") (class "Default")
      (node (ref "BUS2") (pin "4") (pinfunction "5_4") (pintype "passive"))
    )
    (net (code "57") (name "unconnected-(BUS2-6-Pad5)") (class "Default")
      (node (ref "BUS2") (pin "5") (pinfunction "6_5") (pintype "passive"))
    )
    (net (code "58") (name "unconnected-(BUS3-2V5-Pad2V5@2)") (class "Default")
      (node (ref "BUS3") (pin "2V5@2") (pinfunction "2V5_2V5@2") (pintype "passive"))
    )
    (net (code "59") (name "unconnected-(BUS3-5-Pad4)") (class "Default")
      (node (ref "BUS3") (pin "4") (pinfunction "5_4") (pintype "passive"))
    )
    (net (code "60") (name "unconnected-(BUS3-6-Pad5)") (class "Default")
      (node (ref "BUS3") (pin "5") (pinfunction "6_5") (pintype "passive"))
    )
    (net (code "61") (name "unconnected-(BUS4-2V5-Pad2V5@2)") (class "Default")
      (node (ref "BUS4") (pin "2V5@2") (pinfunction "2V5_2V5@2") (pintype "passive"))
    )
    (net (code "62") (name "unconnected-(BUS4-5-Pad4)") (class "Default")
      (node (ref "BUS4") (pin "4") (pinfunction "5_4") (pintype "passive"))
    )
    (net (code "63") (name "unconnected-(BUS4-6-Pad5)") (class "Default")
      (node (ref "BUS4") (pin "5") (pinfunction "6_5") (pintype "passive"))
    )
    (net (code "64") (name "unconnected-(CONN2B-USBID-PadID)") (class "Default")
      (node (ref "CONN2") (pin "ID") (pinfunction "USBID_ID") (pintype "bidirectional"))
    )
    (net (code "65") (name "unconnected-(JP1-Pad1)") (class "Default")
      (node (ref "JP1") (pin "1") (pinfunction "1_1") (pintype "passive"))
    )
    (net (code "66") (name "unconnected-(JP1-Pad2)") (class "Default")
      (node (ref "JP1") (pin "2") (pinfunction "2_2") (pintype "passive"))
    )
    (net (code "67") (name "unconnected-(JP1-Pad3)") (class "Default")
      (node (ref "JP1") (pin "3") (pinfunction "3_3") (pintype "passive"))
    )
    (net (code "68") (name "unconnected-(JP1-Pad4)") (class "Default")
      (node (ref "JP1") (pin "4") (pinfunction "4_4") (pintype "passive"))
    )
    (net (code "69") (name "unconnected-(JP1-Pad5)") (class "Default")
      (node (ref "JP1") (pin "5") (pinfunction "5_5") (pintype "passive"))
    )
    (net (code "70") (name "unconnected-(JP1-Pad6)") (class "Default")
      (node (ref "JP1") (pin "6") (pinfunction "6_6") (pintype "passive"))
    )
    (net (code "71") (name "unconnected-(JP1-Pad7)") (class "Default")
      (node (ref "JP1") (pin "7") (pinfunction "7_7") (pintype "passive"))
    )
    (net (code "72") (name "unconnected-(JP1-Pad8)") (class "Default")
      (node (ref "JP1") (pin "8") (pinfunction "8_8") (pintype "passive"))
    )
    (net (code "73") (name "unconnected-(JP1-Pad9)") (class "Default")
      (node (ref "JP1") (pin "9") (pinfunction "9_9") (pintype "passive"))
    )
    (net (code "74") (name "unconnected-(JP1-Pad10)") (class "Default")
      (node (ref "JP1") (pin "10") (pinfunction "10_10") (pintype "passive"))
    )
    (net (code "75") (name "unconnected-(JP1-Pad11)") (class "Default")
      (node (ref "JP1") (pin "11") (pinfunction "11_11") (pintype "passive"))
    )
    (net (code "76") (name "unconnected-(JP1-Pad12)") (class "Default")
      (node (ref "JP1") (pin "12") (pinfunction "12_12") (pintype "passive"))
    )
    (net (code "77") (name "unconnected-(JP1-Pad13)") (class "Default")
      (node (ref "JP1") (pin "13") (pinfunction "13_13") (pintype "passive"))
    )
    (net (code "78") (name "unconnected-(JP1-Pad14)") (class "Default")
      (node (ref "JP1") (pin "14") (pinfunction "14_14") (pintype "passive"))
    )
    (net (code "79") (name "unconnected-(JP1-Pad15)") (class "Default")
      (node (ref "JP1") (pin "15") (pinfunction "15_15") (pintype "passive"))
    )
    (net (code "80") (name "unconnected-(JP2-Pad1)") (class "Default")
      (node (ref "JP2") (pin "1") (pinfunction "1_1") (pintype "passive"))
    )
    (net (code "81") (name "unconnected-(JP2-Pad2)") (class "Default")
      (node (ref "JP2") (pin "2") (pinfunction "2_2") (pintype "passive"))
    )
    (net (code "82") (name "unconnected-(JP2-Pad3)") (class "Default")
      (node (ref "JP2") (pin "3") (pinfunction "3_3") (pintype "passive"))
    )
    (net (code "83") (name "unconnected-(JP2-Pad4)") (class "Default")
      (node (ref "JP2") (pin "4") (pinfunction "4_4") (pintype "passive"))
    )
    (net (code "84") (name "unconnected-(JP2-Pad5)") (class "Default")
      (node (ref "JP2") (pin "5") (pinfunction "5_5") (pintype "passive"))
    )
    (net (code "85") (name "unconnected-(JP2-Pad6)") (class "Default")
      (node (ref "JP2") (pin "6") (pinfunction "6_6") (pintype "passive"))
    )
    (net (code "86") (name "unconnected-(JP2-Pad7)") (class "Default")
      (node (ref "JP2") (pin "7") (pinfunction "7_7") (pintype "passive"))
    )
    (net (code "87") (name "unconnected-(JP2-Pad8)") (class "Default")
      (node (ref "JP2") (pin "8") (pinfunction "8_8") (pintype "passive"))
    )
    (net (code "88") (name "unconnected-(JP2-Pad9)") (class "Default")
      (node (ref "JP2") (pin "9") (pinfunction "9_9") (pintype "passive"))
    )
    (net (code "89") (name "unconnected-(JP2-Pad10)") (class "Default")
      (node (ref "JP2") (pin "10") (pinfunction "10_10") (pintype "passive"))
    )
    (net (code "90") (name "unconnected-(JP2-Pad11)") (class "Default")
      (node (ref "JP2") (pin "11") (pinfunction "11_11") (pintype "passive"))
    )
    (net (code "91") (name "unconnected-(JP2-Pad12)") (class "Default")
      (node (ref "JP2") (pin "12") (pinfunction "12_12") (pintype "passive"))
    )
    (net (code "92") (name "unconnected-(JP2-Pad13)") (class "Default")
      (node (ref "JP2") (pin "13") (pinfunction "13_13") (pintype "passive"))
    )
    (net (code "93") (name "unconnected-(JP2-Pad14)") (class "Default")
      (node (ref "JP2") (pin "14") (pinfunction "14_14") (pintype "passive"))
    )
    (net (code "94") (name "unconnected-(JP2-Pad15)") (class "Default")
      (node (ref "JP2") (pin "15") (pinfunction "15_15") (pintype "passive"))
    )
    (net (code "95") (name "unconnected-(JP3-Pad1)") (class "Default")
      (node (ref "JP3") (pin "1") (pinfunction "1_1") (pintype "passive"))
    )
    (net (code "96") (name "unconnected-(JP3-Pad2)") (class "Default")
      (node (ref "JP3") (pin "2") (pinfunction "2_2") (pintype "passive"))
    )
    (net (code "97") (name "unconnected-(JP3-Pad3)") (class "Default")
      (node (ref "JP3") (pin "3") (pinfunction "3_3") (pintype "passive"))
    )
    (net (code "98") (name "unconnected-(JP3-Pad4)") (class "Default")
      (node (ref "JP3") (pin "4") (pinfunction "4_4") (pintype "passive"))
    )
    (net (code "99") (name "unconnected-(JP3-Pad5)") (class "Default")
      (node (ref "JP3") (pin "5") (pinfunction "5_5") (pintype "passive"))
    )
    (net (code "100") (name "unconnected-(JP3-Pad6)") (class "Default")
      (node (ref "JP3") (pin "6") (pinfunction "6_6") (pintype "passive"))
    )
    (net (code "101") (name "unconnected-(JP3-Pad7)") (class "Default")
      (node (ref "JP3") (pin "7") (pinfunction "7_7") (pintype "passive"))
    )
    (net (code "102") (name "unconnected-(JP3-Pad8)") (class "Default")
      (node (ref "JP3") (pin "8") (pinfunction "8_8") (pintype "passive"))
    )
    (net (code "103") (name "unconnected-(JP3-Pad9)") (class "Default")
      (node (ref "JP3") (pin "9") (pinfunction "9_9") (pintype "passive"))
    )
    (net (code "104") (name "unconnected-(JP3-Pad10)") (class "Default")
      (node (ref "JP3") (pin "10") (pinfunction "10_10") (pintype "passive"))
    )
    (net (code "105") (name "unconnected-(JP3-Pad11)") (class "Default")
      (node (ref "JP3") (pin "11") (pinfunction "11_11") (pintype "passive"))
    )
    (net (code "106") (name "unconnected-(JP3-Pad12)") (class "Default")
      (node (ref "JP3") (pin "12") (pinfunction "12_12") (pintype "passive"))
    )
    (net (code "107") (name "unconnected-(JP3-Pad13)") (class "Default")
      (node (ref "JP3") (pin "13") (pinfunction "13_13") (pintype "passive"))
    )
    (net (code "108") (name "unconnected-(JP3-Pad14)") (class "Default")
      (node (ref "JP3") (pin "14") (pinfunction "14_14") (pintype "passive"))
    )
    (net (code "109") (name "unconnected-(JP4-Pad1)") (class "Default")
      (node (ref "JP4") (pin "1") (pinfunction "1_1") (pintype "passive"))
    )
    (net (code "110") (name "unconnected-(JP4-Pad2)") (class "Default")
      (node (ref "JP4") (pin "2") (pinfunction "2_2") (pintype "passive"))
    )
    (net (code "111") (name "unconnected-(JP4-Pad3)") (class "Default")
      (node (ref "JP4") (pin "3") (pinfunction "3_3") (pintype "passive"))
    )
    (net (code "112") (name "unconnected-(JP4-Pad4)") (class "Default")
      (node (ref "JP4") (pin "4") (pinfunction "4_4") (pintype "passive"))
    )
    (net (code "113") (name "unconnected-(S1-Pad4)") (class "Default")
      (node (ref "S1") (pin "4") (pinfunction "4_4") (pintype "bidirectional"))
    )
    (net (code "114") (name "unconnected-(S1-Pad5)") (class "Default")
      (node (ref "S1") (pin "5") (pinfunction "5_5") (pintype "bidirectional"))
    )
    (net (code "115") (name "unconnected-(S1-Pad6)") (class "Default")
      (node (ref "S1") (pin "6") (pinfunction "6_6") (pintype "bidirectional"))
    )
  )
)
